# Voltage_Divider.net
KiCad netlist of a schematic drawn in EAGLE
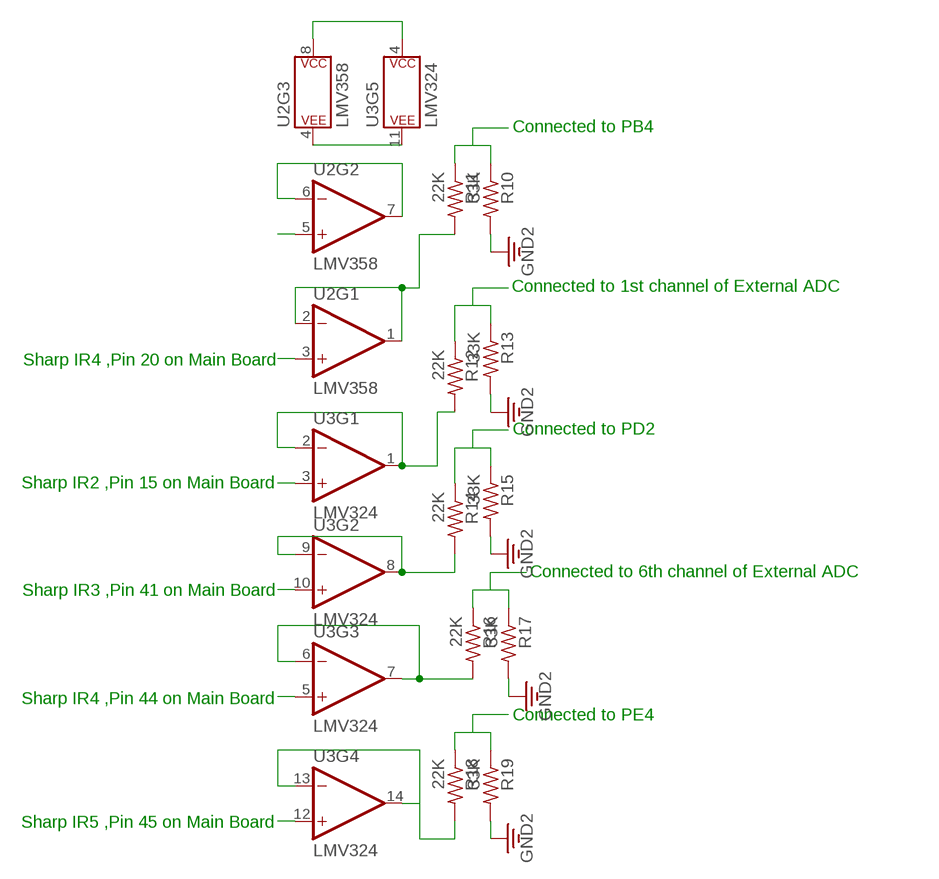
[diagram p0: schematic, sheet 1]

(export (version "E")
  (design (tool "Eeschema 10.0.6"))
  (components
    (comp (ref "R10")
      (value "33K")
      (footprint "eagle-import:M1206")
      (libsource (lib "eagle-import") (part "R-US_M1206"))
    )
    (comp (ref "R11")
      (value "22K")
      (footprint "eagle-import:M1206")
      (libsource (lib "eagle-import") (part "R-US_M1206"))
    )
    (comp (ref "R12")
      (value "22K")
      (footprint "eagle-import:M1206")
      (libsource (lib "eagle-import") (part "R-US_M1206"))
    )
    (comp (ref "R13")
      (value "33K")
      (footprint "eagle-import:M1206")
      (libsource (lib "eagle-import") (part "R-US_M1206"))
    )
    (comp (ref "R14")
      (value "22K")
      (footprint "eagle-import:M1206")
      (libsource (lib "eagle-import") (part "R-US_M1206"))
    )
    (comp (ref "R15")
      (value "33K")
      (footprint "eagle-import:M1206")
      (libsource (lib "eagle-import") (part "R-US_M1206"))
    )
    (comp (ref "R16")
      (value "22K")
      (footprint "eagle-import:M1206")
      (libsource (lib "eagle-import") (part "R-US_M1206"))
    )
    (comp (ref "R17")
      (value "33K")
      (footprint "eagle-import:M1206")
      (libsource (lib "eagle-import") (part "R-US_M1206"))
    )
    (comp (ref "R18")
      (value "22K")
      (footprint "eagle-import:M1206")
      (libsource (lib "eagle-import") (part "R-US_M1206"))
    )
    (comp (ref "R19")
      (value "33K")
      (footprint "eagle-import:M1206")
      (libsource (lib "eagle-import") (part "R-US_M1206"))
    )
    (comp (ref "U2")
      (value "LMV358")
      (footprint "eagle-import:SO08")
      (libsource (lib "eagle-import") (part "LMV358SOIC"))
    )
    (comp (ref "U3")
      (value "LMV324")
      (footprint "eagle-import:SO14")
      (libsource (lib "eagle-import") (part "LMV324"))
    )
  )
  (nets
    (net (code "1") (name "/GND") (class "Default")
      (node (ref "R10") (pin "2") (pinfunction "2_2") (pintype "passive"))
      (node (ref "R13") (pin "2") (pinfunction "2_2") (pintype "passive"))
      (node (ref "R15") (pin "2") (pinfunction "2_2") (pintype "passive"))
      (node (ref "R17") (pin "2") (pinfunction "2_2") (pintype "passive"))
      (node (ref "R19") (pin "2") (pinfunction "2_2") (pintype "passive"))
      (node (ref "U2") (pin "4") (pinfunction "P$V-_4") (pintype "bidirectional"))
      (node (ref "U3") (pin "11") (pinfunction "P$V-_11") (pintype "bidirectional"))
    )
    (net (code "3") (name "Net-(R10-Pad1)") (class "Default")
      (node (ref "R10") (pin "1") (pinfunction "1_1") (pintype "passive"))
      (node (ref "R11") (pin "1") (pinfunction "1_1") (pintype "passive"))
    )
    (net (code "4") (name "Net-(R12-Pad1)") (class "Default")
      (node (ref "R12") (pin "1") (pinfunction "1_1") (pintype "passive"))
      (node (ref "R13") (pin "1") (pinfunction "1_1") (pintype "passive"))
    )
    (net (code "5") (name "Net-(R14-Pad1)") (class "Default")
      (node (ref "R14") (pin "1") (pinfunction "1_1") (pintype "passive"))
      (node (ref "R15") (pin "1") (pinfunction "1_1") (pintype "passive"))
    )
    (net (code "6") (name "Net-(R16-Pad1)") (class "Default")
      (node (ref "R16") (pin "1") (pinfunction "1_1") (pintype "passive"))
      (node (ref "R17") (pin "1") (pinfunction "1_1") (pintype "passive"))
    )
    (net (code "7") (name "Net-(R18-Pad1)") (class "Default")
      (node (ref "R18") (pin "1") (pinfunction "1_1") (pintype "passive"))
      (node (ref "R19") (pin "1") (pinfunction "1_1") (pintype "passive"))
    )
    (net (code "8") (name "Net-(U2A--IN)") (class "Default")
      (node (ref "R11") (pin "2") (pinfunction "2_2") (pintype "passive"))
      (node (ref "U2") (pin "1") (pinfunction "OUT_1") (pintype "output"))
      (node (ref "U2") (pin "2") (pinfunction "-IN_2") (pintype "input"))
    )
    (net (code "9") (name "Net-(U2B--IN)") (class "Default")
      (node (ref "U2") (pin "6") (pinfunction "-IN_6") (pintype "input"))
      (node (ref "U2") (pin "7") (pinfunction "OUT_7") (pintype "output"))
    )
    (net (code "10") (name "Net-(U2C-P$V+)") (class "Default")
      (node (ref "U2") (pin "8") (pinfunction "P$V+_8") (pintype "bidirectional"))
      (node (ref "U3") (pin "4") (pinfunction "P$V+_4") (pintype "bidirectional"))
    )
    (net (code "11") (name "Net-(U3A--IN)") (class "Default")
      (node (ref "R12") (pin "2") (pinfunction "2_2") (pintype "passive"))
      (node (ref "U3") (pin "1") (pinfunction "OUT_1") (pintype "output"))
      (node (ref "U3") (pin "2") (pinfunction "-IN_2") (pintype "input"))
    )
    (net (code "12") (name "Net-(U3B--IN)") (class "Default")
      (node (ref "R14") (pin "2") (pinfunction "2_2") (pintype "passive"))
      (node (ref "U3") (pin "8") (pinfunction "OUT_8") (pintype "output"))
      (node (ref "U3") (pin "9") (pinfunction "-IN_9") (pintype "input"))
    )
    (net (code "13") (name "Net-(U3C--IN)") (class "Default")
      (node (ref "R16") (pin "2") (pinfunction "2_2") (pintype "passive"))
      (node (ref "U3") (pin "6") (pinfunction "-IN_6") (pintype "input"))
      (node (ref "U3") (pin "7") (pinfunction "OUT_7") (pintype "output"))
    )
    (net (code "14") (name "Net-(U3D--IN)") (class "Default")
      (node (ref "R18") (pin "2") (pinfunction "2_2") (pintype "passive"))
      (node (ref "U3") (pin "13") (pinfunction "-IN_13") (pintype "input"))
      (node (ref "U3") (pin "14") (pinfunction "OUT_14") (pintype "output"))
    )
    (net (code "15") (name "unconnected-(U2A-+IN-Pad3)") (class "Default")
      (node (ref "U2") (pin "3") (pinfunction "+IN_3") (pintype "input"))
    )
    (net (code "16") (name "unconnected-(U2B-+IN-Pad5)") (class "Default")
      (node (ref "U2") (pin "5") (pinfunction "+IN_5") (pintype "input"))
    )
    (net (code "17") (name "unconnected-(U3A-+IN-Pad3)") (class "Default")
      (node (ref "U3") (pin "3") (pinfunction "+IN_3") (pintype "input"))
    )
    (net (code "18") (name "unconnected-(U3B-+IN-Pad10)") (class "Default")
      (node (ref "U3") (pin "10") (pinfunction "+IN_10") (pintype "input"))
    )
    (net (code "19") (name "unconnected-(U3C-+IN-Pad5)") (class "Default")
      (node (ref "U3") (pin "5") (pinfunction "+IN_5") (pintype "input"))
    )
    (net (code "20") (name "unconnected-(U3D-+IN-Pad12)") (class "Default")
      (node (ref "U3") (pin "12") (pinfunction "+IN_12") (pintype "input"))
    )
  )
)
